# PiTopUSBHub.net
KiCad netlist of a schematic drawn in Altium Designer
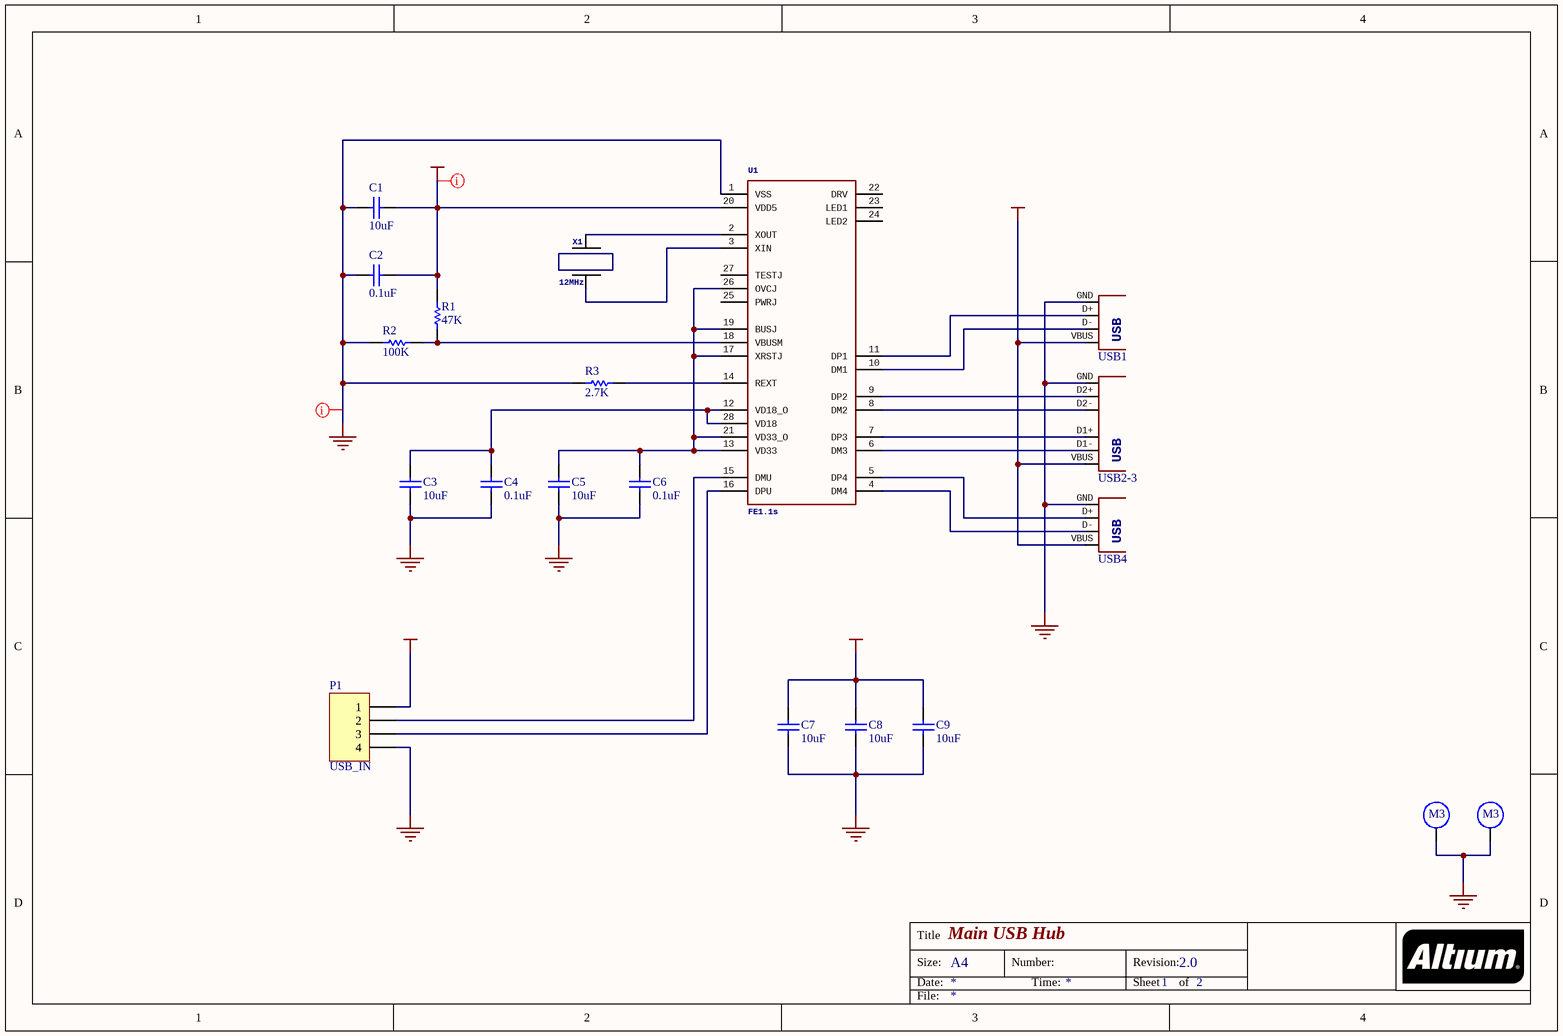
[diagram p0: PiTopUSBHub.SchDoc]

(export (version "E")
  (design (tool "Eeschema 10.0.6"))
  (components
    (comp (ref "C1")
      (value "10uF")
      (footprint "C0805")
      (description "Ceramic Chip Capacitor - Standard")
      (fields (field (name "Comment") "C0805") (field (name "PUBLISHER") "Altium Limited"))
      (libsource (lib "KEMET Chip Capacitor") (part "C0805"))
    )
    (comp (ref "C2")
      (value "0.1uF")
      (footprint "C0805")
      (description "Ceramic Chip Capacitor - Standard")
      (fields (field (name "Comment") "C0805") (field (name "PUBLISHER") "Altium Limited"))
      (libsource (lib "KEMET Chip Capacitor") (part "C0805"))
    )
    (comp (ref "C3")
      (value "10uF")
      (footprint "C0805")
      (description "Ceramic Chip Capacitor - Standard")
      (fields (field (name "Comment") "C0805") (field (name "PUBLISHER") "Altium Limited"))
      (libsource (lib "KEMET Chip Capacitor") (part "C0805"))
    )
    (comp (ref "C4")
      (value "0.1uF")
      (footprint "C0805")
      (description "Ceramic Chip Capacitor - Standard")
      (fields (field (name "Comment") "C0805") (field (name "PUBLISHER") "Altium Limited"))
      (libsource (lib "KEMET Chip Capacitor") (part "C0805"))
    )
    (comp (ref "C5")
      (value "10uF")
      (footprint "C0805")
      (description "Ceramic Chip Capacitor - Standard")
      (fields (field (name "Comment") "C0805") (field (name "PUBLISHER") "Altium Limited"))
      (libsource (lib "KEMET Chip Capacitor") (part "C0805"))
    )
    (comp (ref "C6")
      (value "0.1uF")
      (footprint "C0805")
      (description "Ceramic Chip Capacitor - Standard")
      (fields (field (name "Comment") "C0805") (field (name "PUBLISHER") "Altium Limited"))
      (libsource (lib "KEMET Chip Capacitor") (part "C0805"))
    )
    (comp (ref "C7")
      (value "10uF")
      (footprint "C0805")
      (description "Ceramic Chip Capacitor - Standard")
      (fields (field (name "Comment") "C0805") (field (name "PUBLISHER") "Altium Limited"))
      (libsource (lib "KEMET Chip Capacitor") (part "C0805"))
    )
    (comp (ref "C8")
      (value "10uF")
      (footprint "C0805")
      (description "Ceramic Chip Capacitor - Standard")
      (fields (field (name "Comment") "C0805") (field (name "PUBLISHER") "Altium Limited"))
      (libsource (lib "KEMET Chip Capacitor") (part "C0805"))
    )
    (comp (ref "C9")
      (value "10uF")
      (footprint "C0805")
      (description "Ceramic Chip Capacitor - Standard")
      (fields (field (name "Comment") "C0805") (field (name "PUBLISHER") "Altium Limited"))
      (libsource (lib "KEMET Chip Capacitor") (part "C0805"))
    )
    (comp (ref "H1") (value "M3") (footprint "M3") (libsource (lib "lib") (part "M3")))
    (comp (ref "H2") (value "M3") (footprint "M3") (libsource (lib "lib") (part "M3")))
    (comp (ref "P1")
      (value "USB_IN")
      (footprint "HDR1X4")
      (description "Header, 4-Pin")
      (fields (field (name "PUBLISHER") "Altium Limited"))
      (libsource (lib "Miscellaneous Connectors") (part "Header 4"))
    )
    (comp (ref "R1")
      (value "47K")
      (footprint "R0805")
      (fields (field (name "PUBLISHER") "Altium Limited"))
      (libsource (lib "lib") (part "R0805"))
    )
    (comp (ref "R2")
      (value "100K")
      (footprint "R0805")
      (fields (field (name "PUBLISHER") "Altium Limited"))
      (libsource (lib "lib") (part "R0805"))
    )
    (comp (ref "R3")
      (value "2.7K")
      (footprint "R0805")
      (fields (field (name "PUBLISHER") "Altium Limited"))
      (libsource (lib "lib") (part "R0805"))
    )
    (comp (ref "U1")
      (value "FE1.1S")
      (footprint "FE1.1S_SSOP-28")
      (fields (field (name "FE1.1S") "FE1.1s"))
      (libsource (lib "lib") (part "FE1.1S"))
    )
    (comp (ref "USB1")
      (value "USBA-PTH")
      (footprint "USB-A-F-PTH")
      (fields (field (name "USB") "USB"))
      (libsource (lib "lib") (part "USBA-PTH"))
    )
    (comp (ref "USB2-3")
      (value "USBA2x-PTH")
      (footprint "USB-A-2x-F-PTH")
      (fields (field (name "USB") "USB"))
      (libsource (lib "lib") (part "USBA2x-PTH"))
    )
    (comp (ref "USB4")
      (value "USBA-PTH")
      (footprint "USB-A-F-PTH")
      (fields (field (name "USB") "USB"))
      (libsource (lib "lib") (part "USBA-PTH"))
    )
    (comp (ref "X1")
      (value "12MHz")
      (footprint "XTAL_G5032")
      (description "PTH: ...   SMD: ...   Cylinder: CMR200T-32.768KDZBT")
      (libsource (lib "lib") (part "CRYSTALHC49UP"))
    )
  )
  (nets
    (net (code "1") (name "GND") (class "Default")
      (node (ref "C1") (pin "2") (pinfunction "2_2") (pintype "passive"))
      (node (ref "C2") (pin "2") (pinfunction "2_2") (pintype "passive"))
      (node (ref "C3") (pin "2") (pinfunction "2_2") (pintype "passive"))
      (node (ref "C4") (pin "2") (pinfunction "2_2") (pintype "passive"))
      (node (ref "C5") (pin "2") (pinfunction "2_2") (pintype "passive"))
      (node (ref "C6") (pin "2") (pinfunction "2_2") (pintype "passive"))
      (node (ref "C7") (pin "2") (pinfunction "2_2") (pintype "passive"))
      (node (ref "C8") (pin "2") (pinfunction "2_2") (pintype "passive"))
      (node (ref "C9") (pin "2") (pinfunction "2_2") (pintype "passive"))
      (node (ref "H1") (pin "1") (pinfunction "1_1") (pintype "passive"))
      (node (ref "H2") (pin "1") (pinfunction "1_1") (pintype "passive"))
      (node (ref "P1") (pin "4") (pinfunction "4_4") (pintype "passive"))
      (node (ref "R2") (pin "2") (pinfunction "2_2") (pintype "passive"))
      (node (ref "R3") (pin "1") (pinfunction "1_1") (pintype "passive"))
      (node (ref "U1") (pin "1") (pinfunction "VSS_1") (pintype "passive"))
      (node (ref "USB1") (pin "GND") (pinfunction "GND_GND") (pintype "passive"))
      (node (ref "USB2-3") (pin "GND") (pinfunction "GND_GND") (pintype "passive"))
      (node (ref "USB4") (pin "GND") (pinfunction "GND_GND") (pintype "passive"))
    )
    (net (code "2") (name "Net-(U1-BUSJ)") (class "Default")
      (node (ref "C5") (pin "1") (pinfunction "1_1") (pintype "passive"))
      (node (ref "C6") (pin "1") (pinfunction "1_1") (pintype "passive"))
      (node (ref "U1") (pin "13") (pinfunction "VD33_13") (pintype "passive"))
      (node (ref "U1") (pin "17") (pinfunction "XRSTJ_17") (pintype "passive"))
      (node (ref "U1") (pin "19") (pinfunction "BUSJ_19") (pintype "passive"))
      (node (ref "U1") (pin "21") (pinfunction "VD33_O_21") (pintype "passive"))
      (node (ref "U1") (pin "26") (pinfunction "OVCJ_26") (pintype "passive"))
    )
    (net (code "3") (name "Net-(U1-DM1)") (class "Default")
      (node (ref "U1") (pin "10") (pinfunction "DM1_10") (pintype "passive"))
      (node (ref "USB1") (pin "D-") (pinfunction "D-_D-") (pintype "passive"))
    )
    (net (code "4") (name "Net-(U1-DM2)") (class "Default")
      (node (ref "U1") (pin "8") (pinfunction "DM2_8") (pintype "passive"))
      (node (ref "USB2-3") (pin "D2-") (pinfunction "D2-_D2-") (pintype "passive"))
    )
    (net (code "5") (name "Net-(U1-DM3)") (class "Default")
      (node (ref "U1") (pin "6") (pinfunction "DM3_6") (pintype "passive"))
      (node (ref "USB2-3") (pin "D1-") (pinfunction "D1-_D1-") (pintype "passive"))
    )
    (net (code "6") (name "Net-(U1-DM4)") (class "Default")
      (node (ref "U1") (pin "4") (pinfunction "DM4_4") (pintype "passive"))
      (node (ref "USB4") (pin "D-") (pinfunction "D-_D-") (pintype "passive"))
    )
    (net (code "7") (name "Net-(U1-DMU)") (class "Default")
      (node (ref "P1") (pin "2") (pinfunction "2_2") (pintype "passive"))
      (node (ref "U1") (pin "15") (pinfunction "DMU_15") (pintype "passive"))
    )
    (net (code "8") (name "Net-(U1-DP1)") (class "Default")
      (node (ref "U1") (pin "11") (pinfunction "DP1_11") (pintype "passive"))
      (node (ref "USB1") (pin "D+") (pinfunction "D+_D+") (pintype "passive"))
    )
    (net (code "9") (name "Net-(U1-DP2)") (class "Default")
      (node (ref "U1") (pin "9") (pinfunction "DP2_9") (pintype "passive"))
      (node (ref "USB2-3") (pin "D2+") (pinfunction "D2+_D2+") (pintype "passive"))
    )
    (net (code "10") (name "Net-(U1-DP3)") (class "Default")
      (node (ref "U1") (pin "7") (pinfunction "DP3_7") (pintype "passive"))
      (node (ref "USB2-3") (pin "D1+") (pinfunction "D1+_D1+") (pintype "passive"))
    )
    (net (code "11") (name "Net-(U1-DP4)") (class "Default")
      (node (ref "U1") (pin "5") (pinfunction "DP4_5") (pintype "passive"))
      (node (ref "USB4") (pin "D+") (pinfunction "D+_D+") (pintype "passive"))
    )
    (net (code "12") (name "Net-(U1-DPU)") (class "Default")
      (node (ref "P1") (pin "3") (pinfunction "3_3") (pintype "passive"))
      (node (ref "U1") (pin "16") (pinfunction "DPU_16") (pintype "passive"))
    )
    (net (code "13") (name "Net-(U1-REXT)") (class "Default")
      (node (ref "R3") (pin "2") (pinfunction "2_2") (pintype "passive"))
      (node (ref "U1") (pin "14") (pinfunction "REXT_14") (pintype "passive"))
    )
    (net (code "14") (name "Net-(U1-VBUSM)") (class "Default")
      (node (ref "R1") (pin "2") (pinfunction "2_2") (pintype "passive"))
      (node (ref "R2") (pin "1") (pinfunction "1_1") (pintype "passive"))
      (node (ref "U1") (pin "18") (pinfunction "VBUSM_18") (pintype "passive"))
    )
    (net (code "15") (name "Net-(U1-VD18)") (class "Default")
      (node (ref "C3") (pin "1") (pinfunction "1_1") (pintype "passive"))
      (node (ref "C4") (pin "1") (pinfunction "1_1") (pintype "passive"))
      (node (ref "U1") (pin "12") (pinfunction "VD18_O_12") (pintype "passive"))
      (node (ref "U1") (pin "28") (pinfunction "VD18_28") (pintype "passive"))
    )
    (net (code "16") (name "Net-(U1-XIN)") (class "Default")
      (node (ref "U1") (pin "3") (pinfunction "XIN_3") (pintype "passive"))
      (node (ref "X1") (pin "1") (pinfunction "1_1") (pintype "passive"))
    )
    (net (code "17") (name "Net-(U1-XOUT)") (class "Default")
      (node (ref "U1") (pin "2") (pinfunction "XOUT_2") (pintype "passive"))
      (node (ref "X1") (pin "2") (pinfunction "2_2") (pintype "passive"))
    )
    (net (code "18") (name "VCC") (class "Default")
      (node (ref "C1") (pin "1") (pinfunction "1_1") (pintype "passive"))
      (node (ref "C2") (pin "1") (pinfunction "1_1") (pintype "passive"))
      (node (ref "C7") (pin "1") (pinfunction "1_1") (pintype "passive"))
      (node (ref "C8") (pin "1") (pinfunction "1_1") (pintype "passive"))
      (node (ref "C9") (pin "1") (pinfunction "1_1") (pintype "passive"))
      (node (ref "P1") (pin "1") (pinfunction "1_1") (pintype "passive"))
      (node (ref "R1") (pin "1") (pinfunction "1_1") (pintype "passive"))
      (node (ref "U1") (pin "20") (pinfunction "VDD5_20") (pintype "passive"))
      (node (ref "USB1") (pin "VBUS") (pinfunction "VBUS_VBUS") (pintype "passive"))
      (node (ref "USB2-3") (pin "VBUS") (pinfunction "VBUS_VBUS") (pintype "passive"))
      (node (ref "USB4") (pin "VBUS") (pinfunction "VBUS_VBUS") (pintype "passive"))
    )
    (net (code "19") (name "unconnected-(U1-DRV-Pad22)") (class "Default")
      (node (ref "U1") (pin "22") (pinfunction "DRV_22") (pintype "passive"))
    )
    (net (code "20") (name "unconnected-(U1-LED1-Pad23)") (class "Default")
      (node (ref "U1") (pin "23") (pinfunction "LED1_23") (pintype "passive"))
    )
    (net (code "21") (name "unconnected-(U1-LED2-Pad24)") (class "Default")
      (node (ref "U1") (pin "24") (pinfunction "LED2_24") (pintype "passive"))
    )
    (net (code "22") (name "unconnected-(U1-PWRJ-Pad25)") (class "Default")
      (node (ref "U1") (pin "25") (pinfunction "PWRJ_25") (pintype "passive"))
    )
    (net (code "23") (name "unconnected-(U1-TESTJ-Pad27)") (class "Default")
      (node (ref "U1") (pin "27") (pinfunction "TESTJ_27") (pintype "passive"))
    )
  )
)
